# ultrasonic_tx.net
KiCad netlist of a schematic drawn in Altium Designer
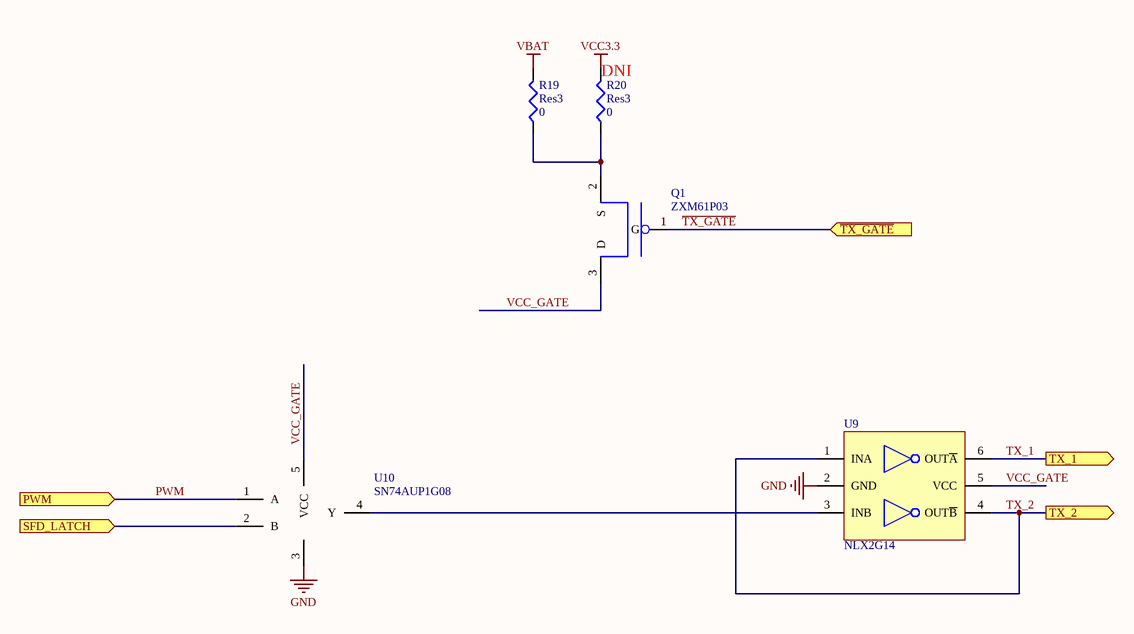
[diagram p0: ultrasonic_tx.SchDoc]

(export (version "E")
  (design (tool "Eeschema 10.0.6"))
  (components
    (comp (ref "Q1")
      (value "ZXM61P03")
      (footprint "SOT23-3N")
      (description "30V P-CHANNEL ENHANCEMENT MODE MOSFET")
      (libsource (lib "ultrasounic") (part "ZXM61P03"))
    )
    (comp (ref "R19")
      (value "Res3")
      (footprint "J1-0603")
      (description "Resistor")
      (fields (field (name "ALTIUM_VALUE") "0") (field (name "PUBLISHER") "Altium Limited"))
      (libsource (lib "Miscellaneous Devices") (part "Res3"))
    )
    (comp (ref "R20")
      (value "Res3")
      (footprint "J1-0603")
      (description "Resistor")
      (fields (field (name "ALTIUM_VALUE") "0") (field (name "PUBLISHER") "Altium Limited"))
      (libsource (lib "Miscellaneous Devices") (part "Res3"))
    )
    (comp (ref "U9")
      (value "NLX2G14")
      (footprint "ULLGA6")
      (description "Dual Schmitt-Trigger  Inverter")
      (libsource (lib "ultrasounic") (part "NLX2G14"))
    )
    (comp (ref "U10")
      (value "SN74AUP1G08")
      (footprint "SC70-6")
      (description "LOW-POWER SINGLE 2-INPUT POSITIVE-AND GATE")
      (libsource (lib "ultrasounic") (part "SN74AUP1G08"))
    )
  )
  (nets
    (net (code "1") (name "/PWM") (class "Default")
      (node (ref "U10") (pin "1") (pinfunction "A_1") (pintype "passive"))
    )
    (net (code "2") (name "/SFD_LATCH") (class "Default")
      (node (ref "U10") (pin "2") (pinfunction "B_2") (pintype "passive"))
    )
    (net (code "3") (name "/TX_1") (class "Default")
      (node (ref "U9") (pin "6") (pinfunction "OUT~{A}_6") (pintype "passive"))
    )
    (net (code "4") (name "/TX_2") (class "Default")
      (node (ref "U9") (pin "1") (pinfunction "INA_1") (pintype "passive"))
      (node (ref "U9") (pin "4") (pinfunction "OUT~{B}_4") (pintype "passive"))
    )
    (net (code "5") (name "/VCC_GATE") (class "Default")
      (node (ref "Q1") (pin "3") (pinfunction "D_3") (pintype "passive"))
      (node (ref "U10") (pin "5") (pinfunction "VCC_5") (pintype "passive"))
      (node (ref "U9") (pin "5") (pinfunction "VCC_5") (pintype "passive"))
    )
    (net (code "6") (name "/~{TX_GATE}") (class "Default")
      (node (ref "Q1") (pin "1") (pinfunction "G_1") (pintype "passive"))
    )
    (net (code "7") (name "GND") (class "Default")
      (node (ref "U10") (pin "3") (pinfunction "GND_3") (pintype "passive"))
      (node (ref "U9") (pin "2") (pinfunction "GND_2") (pintype "passive"))
    )
    (net (code "8") (name "Net-(Q1-S)") (class "Default")
      (node (ref "Q1") (pin "2") (pinfunction "S_2") (pintype "passive"))
      (node (ref "R19") (pin "1") (pinfunction "1_1") (pintype "passive"))
      (node (ref "R20") (pin "1") (pinfunction "1_1") (pintype "passive"))
    )
    (net (code "9") (name "Net-(U10-Y)") (class "Default")
      (node (ref "U10") (pin "4") (pinfunction "Y_4") (pintype "passive"))
      (node (ref "U9") (pin "3") (pinfunction "INB_3") (pintype "passive"))
    )
    (net (code "10") (name "VBAT") (class "Default")
      (node (ref "R19") (pin "2") (pinfunction "2_2") (pintype "passive"))
    )
    (net (code "11") (name "VCC3.3") (class "Default")
      (node (ref "R20") (pin "2") (pinfunction "2_2") (pintype "passive"))
    )
  )
)
